# design.net
KiCad netlist of a schematic drawn in Altium Designer
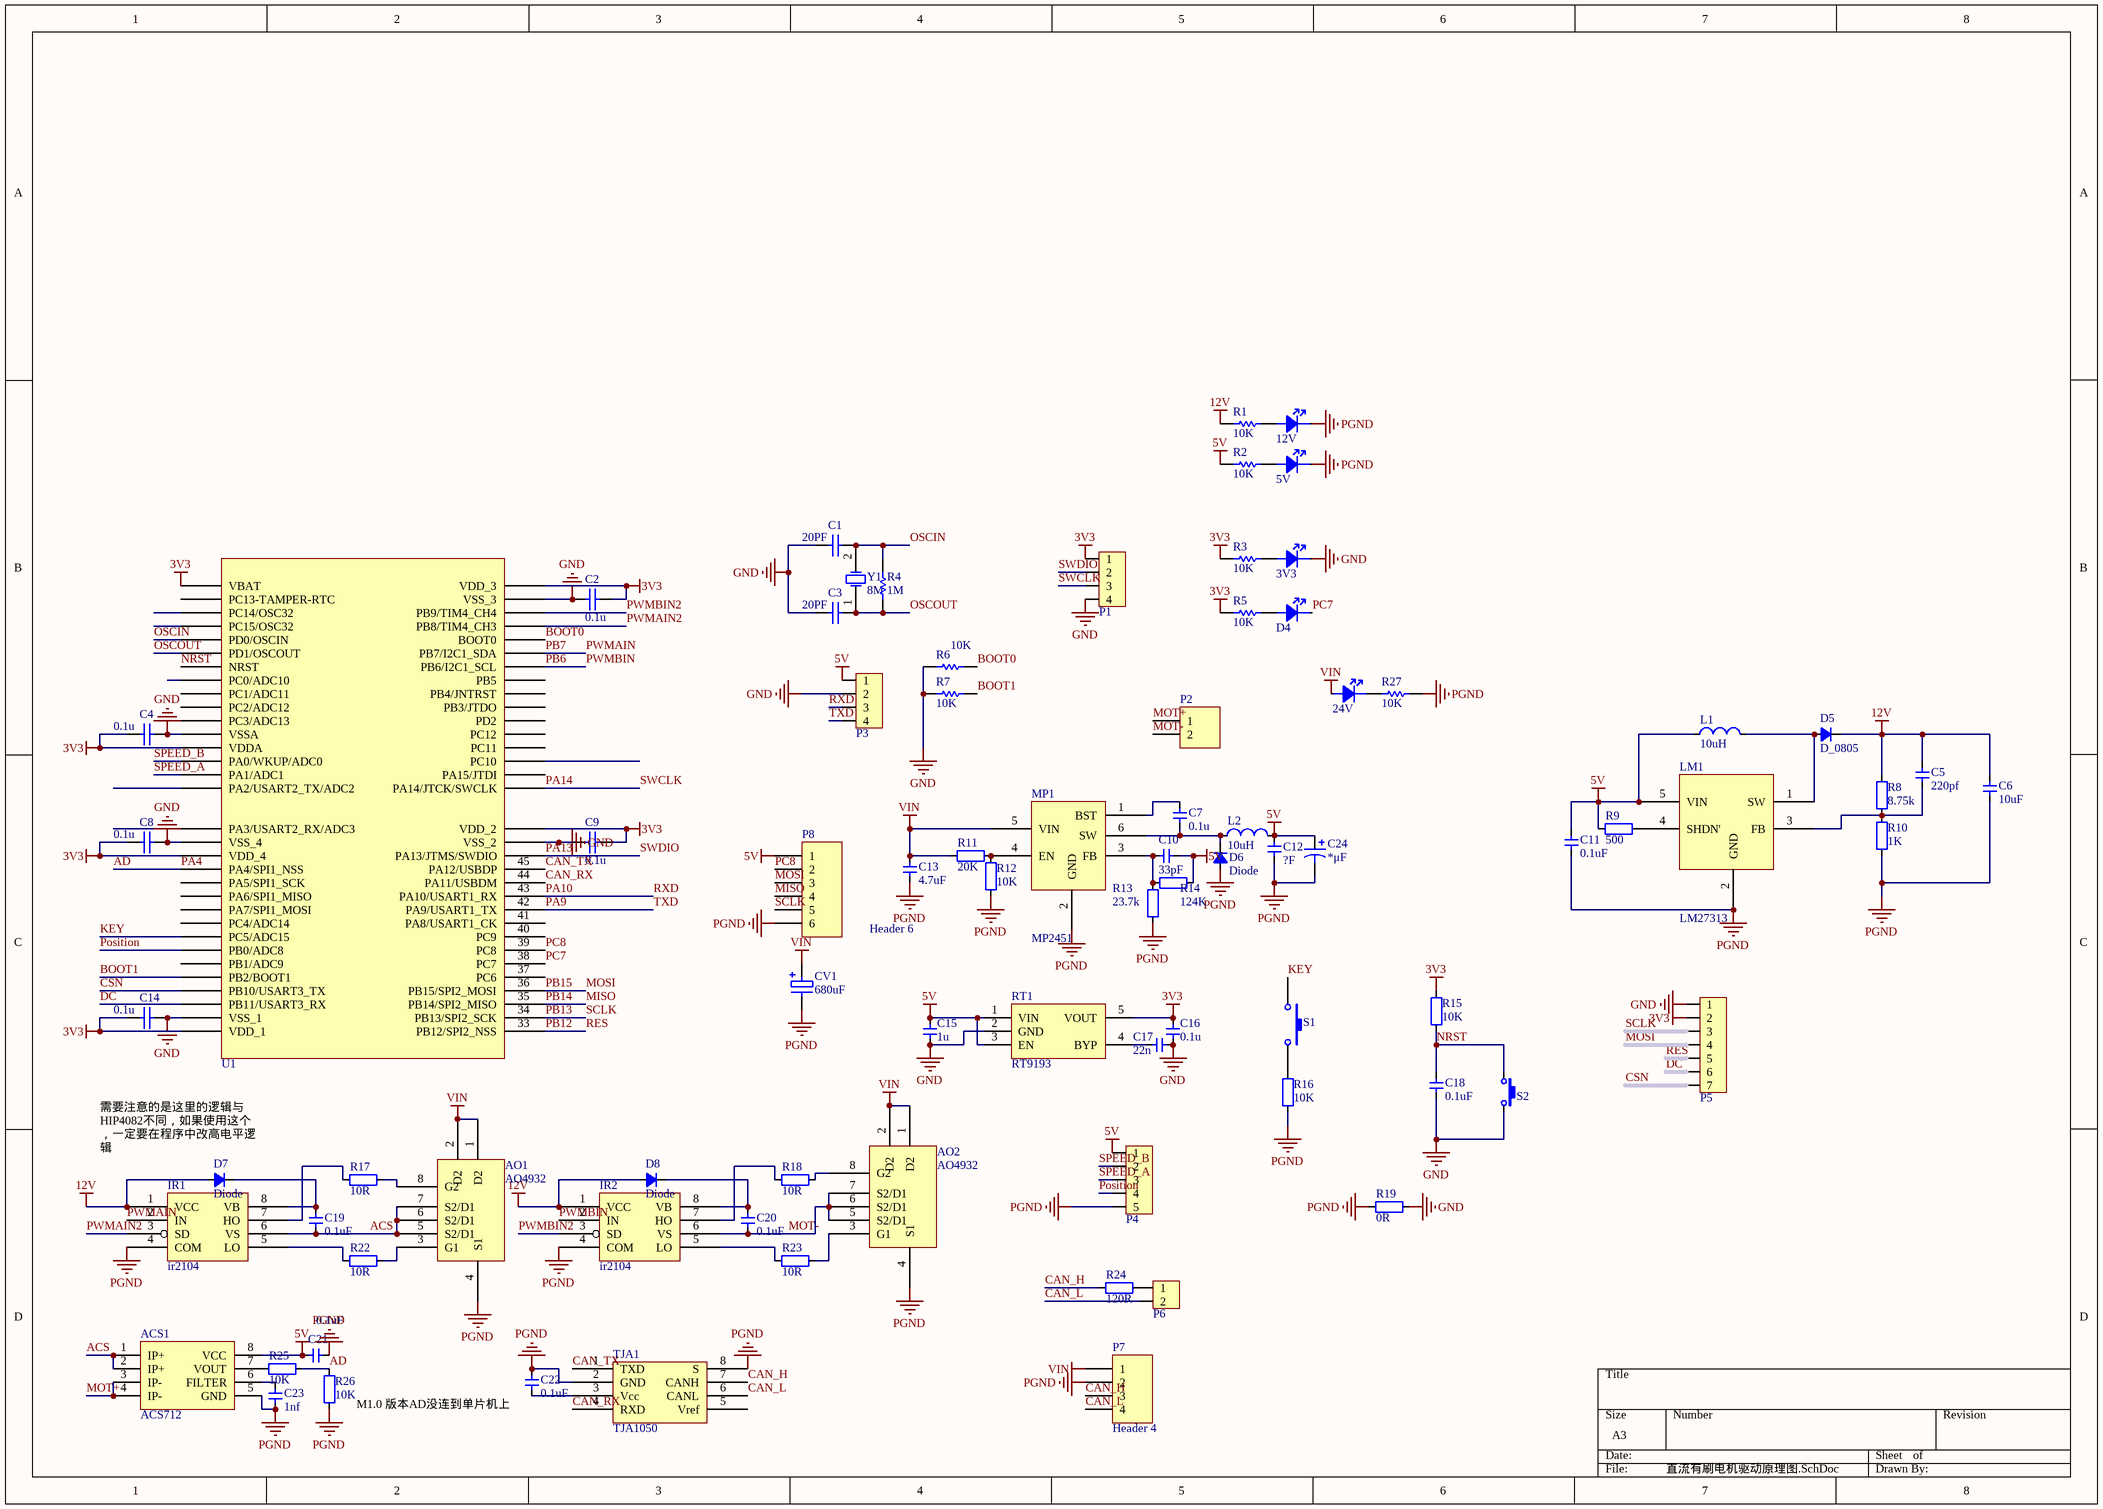
[diagram p0: 直流有刷电机驱动原理图.SchDoc]

(export (version "E")
  (design (tool "Eeschema 10.0.6"))
  (components
    (comp (ref "3V3")
      (value "lED")
      (footprint "0805D")
      (description "LED")
      (libsource (lib "K60-mainboard-v3.1") (part "00-D-LED"))
    )
    (comp (ref "5V")
      (value "lED")
      (footprint "0805D")
      (description "LED")
      (libsource (lib "K60-mainboard-v3.1") (part "00-D-LED"))
    )
    (comp (ref "12V")
      (value "lED")
      (footprint "0805D")
      (description "LED")
      (libsource (lib "K60-mainboard-v3.1") (part "00-D-LED"))
    )
    (comp (ref "24V")
      (value "lED")
      (footprint "0805D")
      (description "LED")
      (libsource (lib "K60-mainboard-v3.1") (part "00-D-LED"))
    )
    (comp (ref "ACS1")
      (value "ACS712")
      (footprint "PCB_IntegratedCircuit:SOP_E150_8")
      (description "Sensor Current")
      (libsource (lib "SCH_IntegratedCircuit") (part "ACS712"))
    )
    (comp (ref "AO1")
      (value "AO4932")
      (footprint "SOP_E150_8")
      (libsource (lib "SCH_Active") (part "AO4932"))
    )
    (comp (ref "AO2")
      (value "AO4932")
      (footprint "SOP_E150_8")
      (libsource (lib "SCH_Active") (part "AO4932"))
    )
    (comp (ref "C1")
      (value "20PF")
      (footprint "CAP-MLCC-0603")
      (description "Capacitor")
      (fields (field (name "Comment") "Cap") (field (name "PUBLISHER") "Altium Limited"))
      (libsource (lib "K60-mainboard-v3.1") (part "Cap_1"))
    )
    (comp (ref "C2")
      (value "0.1u")
      (footprint "CAP-MLCC-0603")
      (description "Capacitor")
      (fields (field (name "Comment") "Cap") (field (name "PUBLISHER") "Altium Limited"))
      (libsource (lib "K60-mainboard-v3.1") (part "Cap_1"))
    )
    (comp (ref "C3")
      (value "20PF")
      (footprint "CAP-MLCC-0603")
      (description "Capacitor")
      (fields (field (name "Comment") "Cap") (field (name "PUBLISHER") "Altium Limited"))
      (libsource (lib "K60-mainboard-v3.1") (part "Cap_1"))
    )
    (comp (ref "C4")
      (value "0.1u")
      (footprint "CAP-MLCC-0603")
      (description "Capacitor")
      (fields (field (name "Comment") "Cap") (field (name "PUBLISHER") "Altium Limited"))
      (libsource (lib "K60-mainboard-v3.1") (part "Cap_1"))
    )
    (comp (ref "C5")
      (value "220pf")
      (footprint "PCB_PassiveCap:CAP_0603")
      (description "Capacitor")
      (fields (field (name "Comment") "Cap_0603"))
      (libsource (lib "SCH_Passive") (part "Cap_0603"))
    )
    (comp (ref "C6")
      (value "10uF")
      (footprint "PCB_PassiveCap:CAP_0603")
      (description "Capacitor")
      (fields (field (name "Comment") "Cap_0603"))
      (libsource (lib "SCH_Passive") (part "Cap_0603"))
    )
    (comp (ref "C7")
      (value "0.1u")
      (footprint "PCB_PassiveCap:CAP_0603")
      (description "Capacitor")
      (fields (field (name "Comment") "Cap_0603"))
      (libsource (lib "SCH_Passive") (part "Cap_0603"))
    )
    (comp (ref "C8")
      (value "0.1u")
      (footprint "CAP-MLCC-0603")
      (description "Capacitor")
      (fields (field (name "Comment") "Cap") (field (name "PUBLISHER") "Altium Limited"))
      (libsource (lib "K60-mainboard-v3.1") (part "Cap_1"))
    )
    (comp (ref "C9")
      (value "0.1u")
      (footprint "CAP-MLCC-0603")
      (description "Capacitor")
      (fields (field (name "Comment") "Cap") (field (name "PUBLISHER") "Altium Limited"))
      (libsource (lib "K60-mainboard-v3.1") (part "Cap_1"))
    )
    (comp (ref "C10")
      (value "33pF")
      (footprint "PCB_PassiveCap:CAP_0603")
      (description "Capacitor")
      (fields (field (name "Comment") "Cap_0603"))
      (libsource (lib "SCH_Passive") (part "Cap_0603"))
    )
    (comp (ref "C11")
      (value "0.1uF")
      (footprint "PCB_PassiveCap:CAP_0603")
      (description "Capacitor")
      (fields (field (name "Comment") "Cap_0603"))
      (libsource (lib "SCH_Passive") (part "Cap_0603"))
    )
    (comp (ref "C12")
      (value "?F")
      (footprint "PCB_PassiveCap:CAP_0603")
      (description "Capacitor")
      (fields (field (name "Comment") "Cap_0603"))
      (libsource (lib "SCH_Passive") (part "Cap_0603"))
    )
    (comp (ref "C13")
      (value "4.7uF")
      (footprint "Libraries_2014_0618:CAP-MLCC-1206")
      (description "Capacitor")
      (fields (field (name "Comment") "Cap_0805"))
      (libsource (lib "SCH_Passive") (part "Cap_0805"))
    )
    (comp (ref "C14")
      (value "0.1u")
      (footprint "CAP-MLCC-0603")
      (description "Capacitor")
      (fields (field (name "Comment") "Cap") (field (name "PUBLISHER") "Altium Limited"))
      (libsource (lib "K60-mainboard-v3.1") (part "Cap_1"))
    )
    (comp (ref "C15")
      (value "1u")
      (footprint "PCB_PassiveCap:CAP_0603")
      (description "Capacitor")
      (fields (field (name "Comment") "Cap_0603"))
      (libsource (lib "SCH_Passive") (part "Cap_0603"))
    )
    (comp (ref "C16")
      (value "0.1u")
      (footprint "PCB_PassiveCap:CAP_0603")
      (description "Capacitor")
      (fields (field (name "Comment") "Cap_0603"))
      (libsource (lib "SCH_Passive") (part "Cap_0603"))
    )
    (comp (ref "C17")
      (value "22n")
      (footprint "PCB_PassiveCap:CAP_0603")
      (description "Capacitor")
      (fields (field (name "Comment") "Cap_0603"))
      (libsource (lib "SCH_Passive") (part "Cap_0603"))
    )
    (comp (ref "C18")
      (value "0.1uF")
      (footprint "PCB_PassiveCap:CAP_0603")
      (description "Capacitor")
      (fields (field (name "Comment") "Cap_0603"))
      (libsource (lib "SCH_Passive") (part "Cap_0603"))
    )
    (comp (ref "C19")
      (value "0.1uF")
      (footprint "PCB_PassiveCap:CAP_0603")
      (description "Capacitor")
      (fields (field (name "Comment") "Cap_0603"))
      (libsource (lib "SCH_Passive") (part "Cap_0603"))
    )
    (comp (ref "C20")
      (value "0.1uF")
      (footprint "PCB_PassiveCap:CAP_0603")
      (description "Capacitor")
      (fields (field (name "Comment") "Cap_0603"))
      (libsource (lib "SCH_Passive") (part "Cap_0603"))
    )
    (comp (ref "C21")
      (value "0.1uF")
      (footprint "PCB_PassiveCap:CAP_0603")
      (description "Capacitor")
      (fields (field (name "Comment") "Cap_0603"))
      (libsource (lib "SCH_Passive") (part "Cap_0603"))
    )
    (comp (ref "C22")
      (value "0.1uF")
      (footprint "PCB_PassiveCap:CAP_0603")
      (description "Capacitor")
      (fields (field (name "Comment") "Cap_0603"))
      (libsource (lib "SCH_Passive") (part "Cap_0603"))
    )
    (comp (ref "C23")
      (value "1nf")
      (footprint "PCB_PassiveCap:CAP_0603")
      (description "Capacitor")
      (fields (field (name "Comment") "Cap_0603"))
      (libsource (lib "SCH_Passive") (part "Cap_0603"))
    )
    (comp (ref "C24")
      (value "*μF")
      (footprint "CAP-TAN-3216/CAPA")
      (description "钽电容")
      (fields (field (name "PUBLISHER") "Altium Limited"))
      (libsource (lib "Libraries_2014_0618") (part "CAP-TAN"))
    )
    (comp (ref "CV1")
      (value "680uF")
      (footprint "C_ELE2")
      (description "电解电容")
      (fields (field (name "PUBLISHER") "Altium Limited"))
      (libsource (lib "Libraries_2014_0618") (part "CAP-ELE"))
    )
    (comp (ref "D4")
      (value "lED")
      (footprint "0805D")
      (description "LED")
      (libsource (lib "K60-mainboard-v3.1") (part "00-D-LED"))
    )
    (comp (ref "D5")
      (value "D_0805")
      (footprint "LED_0805_YELLOW")
      (libsource (lib "SCH_Active") (part "D_0805"))
    )
    (comp (ref "D6") (value "Diode") (footprint "LED_0805_RED") (libsource (lib "SCH_Active") (part "Diode")))
    (comp (ref "D7") (value "Diode") (footprint "LED_0805_RED") (libsource (lib "SCH_Active") (part "Diode")))
    (comp (ref "D8") (value "Diode") (footprint "LED_0805_RED") (libsource (lib "SCH_Active") (part "Diode")))
    (comp (ref "IR1")
      (value "ir2104")
      (footprint "SOP_E150_8")
      (libsource (lib "SCH_IntegratedCircuit") (part "ir2104"))
    )
    (comp (ref "IR2")
      (value "ir2104")
      (footprint "SOP_E150_8")
      (libsource (lib "SCH_IntegratedCircuit") (part "ir2104"))
    )
    (comp (ref "L1")
      (value "10uH")
      (footprint "IND_CD52")
      (description "Inductor")
      (fields (field (name "Comment") "Ind_CD32"))
      (libsource (lib "SCH_Passive") (part "Ind_CD32"))
    )
    (comp (ref "L2")
      (value "10uH")
      (footprint "IND_CD52")
      (description "Inductor")
      (fields (field (name "Comment") "Ind_CD32"))
      (libsource (lib "SCH_Passive") (part "Ind_CD32"))
    )
    (comp (ref "LM1")
      (value "LM27313")
      (footprint "SOT23-5")
      (libsource (lib "SCH_IntegratedCircuit") (part "LM27313"))
    )
    (comp (ref "MP1")
      (value "MP2451")
      (footprint "SOT23-6")
      (libsource (lib "SCH_IntegratedCircuit") (part "MP2451"))
    )
    (comp (ref "P1")
      (value "HDR1x4_2.54")
      (footprint "PCB_ConnectorHDR:HDR1x4_2.54_180")
      (description "Header")
      (libsource (lib "SCH_ConnectorHDR") (part "HDR1x4_2.54"))
    )
    (comp (ref "P2")
      (value "Header 2")
      (footprint "Green_2P")
      (description "Header, 2-Pin")
      (fields (field (name "PUBLISHER") "Altium Limited"))
      (libsource (lib "Libraries_2014_0618") (part "Header 2"))
    )
    (comp (ref "P3")
      (value "HDR1x4_2.54")
      (footprint "PCB_ConnectorHDR:HDR1x4_2.54_180")
      (description "Header")
      (libsource (lib "SCH_ConnectorHDR") (part "HDR1x4_2.54"))
    )
    (comp (ref "P4")
      (value "HDR1x5_2.54")
      (footprint "PCB_ConnectorHDR:HDR1X5_2.54_180")
      (description "Header")
      (libsource (lib "SCH_ConnectorHDR") (part "HDR1x5_2.54"))
    )
    (comp (ref "P5")
      (value "HDR1x7_2.54")
      (footprint "PCB_ConnectorHDR:HDR1X7_2.54_180")
      (description "Header")
      (libsource (lib "SCH_ConnectorHDR") (part "HDR1x7_2.54T"))
    )
    (comp (ref "P6")
      (value "HDR1x2_2.54")
      (footprint "PCB_ConnectorHDR:HDR1X2_2.54_180")
      (description "Header")
      (libsource (lib "SCH_ConnectorHDR") (part "HDR1x2_2.54"))
    )
    (comp (ref "P7")
      (value "Header 4")
      (footprint "Green_4P")
      (description "Header, 4-Pin")
      (fields (field (name "PUBLISHER") "Altium Limited"))
      (libsource (lib "Libraries_2014_0618") (part "Header 4"))
    )
    (comp (ref "P8")
      (value "Header 6")
      (footprint "HDR1X6_2.54_180")
      (description "Header, 6-Pin")
      (fields (field (name "PUBLISHER") "Altium Limited"))
      (libsource (lib "Libraries_2014_0618") (part "Header 6"))
    )
    (comp (ref "R1")
      (value "10K")
      (footprint "RES-0603")
      (description "Resistor")
      (fields (field (name "Comment") "Res1") (field (name "PUBLISHER") "Altium Limited"))
      (libsource (lib "K60-mainboard-v3.1") (part "Res1_1"))
    )
    (comp (ref "R2")
      (value "10K")
      (footprint "RES-0603")
      (description "Resistor")
      (fields (field (name "Comment") "Res1") (field (name "PUBLISHER") "Altium Limited"))
      (libsource (lib "K60-mainboard-v3.1") (part "Res1_1"))
    )
    (comp (ref "R3")
      (value "10K")
      (footprint "RES-0603")
      (description "Resistor")
      (fields (field (name "Comment") "Res1") (field (name "PUBLISHER") "Altium Limited"))
      (libsource (lib "K60-mainboard-v3.1") (part "Res1_1"))
    )
    (comp (ref "R4")
      (value "1M")
      (footprint "RES-0603")
      (description "Resistor")
      (fields (field (name "Comment") "Res1") (field (name "PUBLISHER") "Altium Limited"))
      (libsource (lib "K60-mainboard-v3.1") (part "Res1_1"))
    )
    (comp (ref "R5")
      (value "10K")
      (footprint "RES-0603")
      (description "Resistor")
      (fields (field (name "Comment") "Res1") (field (name "PUBLISHER") "Altium Limited"))
      (libsource (lib "K60-mainboard-v3.1") (part "Res1_1"))
    )
    (comp (ref "R6")
      (value "10K")
      (footprint "RES-0603")
      (description "Resistor")
      (fields (field (name "Comment") "Res1") (field (name "PUBLISHER") "Altium Limited"))
      (libsource (lib "K60-mainboard-v3.1") (part "Res1_1"))
    )
    (comp (ref "R7")
      (value "10K")
      (footprint "RES-0603")
      (description "Resistor")
      (fields (field (name "Comment") "Res1") (field (name "PUBLISHER") "Altium Limited"))
      (libsource (lib "K60-mainboard-v3.1") (part "Res1_1"))
    )
    (comp (ref "R8")
      (value "8.75k")
      (footprint "PCB_PassiveRes:RES_0603")
      (description "Resistor")
      (fields (field (name "Comment") "Res_0603"))
      (libsource (lib "SCH_Passive") (part "Res_0603"))
    )
    (comp (ref "R9")
      (value "500")
      (footprint "PCB_PassiveRes:RES_0603")
      (description "Resistor")
      (fields (field (name "Comment") "Res_0603"))
      (libsource (lib "") (part "Res_0603_2"))
    )
    (comp (ref "R10")
      (value "1K")
      (footprint "PCB_PassiveRes:RES_0603")
      (description "Resistor")
      (fields (field (name "Comment") "Res_0603"))
      (libsource (lib "SCH_Passive") (part "Res_0603"))
    )
    (comp (ref "R11")
      (value "20K")
      (footprint "PCB_PassiveRes:RES_0603")
      (description "Resistor")
      (fields (field (name "Comment") "Res_0603"))
      (libsource (lib "") (part "Res_0603_3"))
    )
    (comp (ref "R12")
      (value "10K")
      (footprint "PCB_PassiveRes:RES_0603")
      (description "Resistor")
      (fields (field (name "Comment") "Res_0603"))
      (libsource (lib "SCH_Passive") (part "Res_0603"))
    )
    (comp (ref "R13")
      (value "23.7k")
      (footprint "PCB_PassiveRes:RES_0603")
      (description "Resistor")
      (fields (field (name "Comment") "Res_0603"))
      (libsource (lib "SCH_Passive") (part "Res_0603"))
    )
    (comp (ref "R14")
      (value "124K")
      (footprint "PCB_PassiveRes:RES_0603")
      (description "Resistor")
      (fields (field (name "Comment") "Res_0603"))
      (libsource (lib "") (part "Res_0603_3"))
    )
    (comp (ref "R15")
      (value "10K")
      (footprint "PCB_PassiveRes:RES_0603")
      (description "Resistor")
      (fields (field (name "Comment") "Res_0603"))
      (libsource (lib "") (part "Res_0603_1"))
    )
    (comp (ref "R16")
      (value "10K")
      (footprint "PCB_PassiveRes:RES_0603")
      (description "Resistor")
      (fields (field (name "Comment") "Res_0603"))
      (libsource (lib "SCH_Passive") (part "Res_0603"))
    )
    (comp (ref "R17")
      (value "10R")
      (footprint "PCB_PassiveRes:RES_0603")
      (description "Resistor")
      (fields (field (name "Comment") "Res_0603"))
      (libsource (lib "") (part "Res_0603_3"))
    )
    (comp (ref "R18")
      (value "10R")
      (footprint "PCB_PassiveRes:RES_0603")
      (description "Resistor")
      (fields (field (name "Comment") "Res_0603"))
      (libsource (lib "") (part "Res_0603_3"))
    )
    (comp (ref "R19")
      (value "0R")
      (footprint "PCB_PassiveRes:RES_0603")
      (description "Resistor")
      (fields (field (name "Comment") "Res_0603"))
      (libsource (lib "") (part "Res_0603_2"))
    )
    (comp (ref "R22")
      (value "10R")
      (footprint "PCB_PassiveRes:RES_0603")
      (description "Resistor")
      (fields (field (name "Comment") "Res_0603"))
      (libsource (lib "") (part "Res_0603_3"))
    )
    (comp (ref "R23")
      (value "10R")
      (footprint "PCB_PassiveRes:RES_0603")
      (description "Resistor")
      (fields (field (name "Comment") "Res_0603"))
      (libsource (lib "") (part "Res_0603_3"))
    )
    (comp (ref "R24")
      (value "120R")
      (footprint "PCB_PassiveRes:RES_0603")
      (description "Resistor")
      (fields (field (name "Comment") "Res_0603"))
      (libsource (lib "") (part "Res_0603_2"))
    )
    (comp (ref "R25")
      (value "10K")
      (footprint "PCB_PassiveRes:RES_0603")
      (description "Resistor")
      (fields (field (name "Comment") "Res_0603"))
      (libsource (lib "") (part "Res_0603_3"))
    )
    (comp (ref "R26")
      (value "10K")
      (footprint "PCB_PassiveRes:RES_0603")
      (description "Resistor")
      (fields (field (name "Comment") "Res_0603"))
      (libsource (lib "") (part "Res_0603_1"))
    )
    (comp (ref "R27")
      (value "10K")
      (footprint "RES-0603")
      (description "Resistor")
      (fields (field (name "Comment") "Res1") (field (name "PUBLISHER") "Altium Limited"))
      (libsource (lib "K60-mainboard-v3.1") (part "Res1_1"))
    )
    (comp (ref "RT1")
      (value "RT9193")
      (footprint "PCB_IntegratedCircuit:SOT23-5")
      (description "Power")
      (libsource (lib "SCH_IntegratedCircuit") (part "RT9193"))
    )
    (comp (ref "S1")
      (value "SW-PB")
      (footprint "key - duplicate")
      (description "Switch")
      (fields (field (name "PUBLISHER") "Altium Limited"))
      (libsource (lib "附加元件") (part "SW-PB"))
    )
    (comp (ref "S2")
      (value "ButtonTACT_3x4x2_180")
      (footprint "PCB_Switch:ButtonTACT_3x4x2_180H")
      (description "Button")
      (libsource (lib "SCH_Switch") (part "ButtonTACT_3x4x2_180"))
    )
    (comp (ref "TJA1")
      (value "TJA1050")
      (footprint "SOP_E150_8")
      (libsource (lib "SCH_IntegratedCircuit") (part "TJA1050"))
    )
    (comp (ref "U1")
      (value "STM32F103RC")
      (footprint "LQFP_P0.5_64")
      (description "MCU")
      (libsource (lib "SCH_IntegratedCircuit") (part "STM32F103RC"))
    )
    (comp (ref "Y1")
      (value "8M")
      (footprint "PCB_Oscillator:XT_5032_2")
      (description "Crystal Oscillator")
      (fields (field (name "PUBLISHER") "Altium Limited"))
      (libsource (lib "Libraries_2014_0618") (part "C-Osc"))
    )
  )
  (nets
    (net (code "1") (name "/ACS") (class "Default")
      (node (ref "ACS1") (pin "1") (pinfunction "IP+_1") (pintype "passive"))
      (node (ref "ACS1") (pin "2") (pinfunction "IP+_2") (pintype "passive"))
      (node (ref "AO1") (pin "5") (pinfunction "S2/D1_5") (pintype "passive"))
      (node (ref "AO1") (pin "6") (pinfunction "S2/D1_6") (pintype "passive"))
      (node (ref "AO1") (pin "7") (pinfunction "S2/D1_7") (pintype "passive"))
      (node (ref "C19") (pin "2") (pinfunction "2_2") (pintype "passive"))
      (node (ref "IR1") (pin "6") (pinfunction "VS_6") (pintype "passive"))
    )
    (net (code "2") (name "/AD") (class "Default")
      (node (ref "R25") (pin "2") (pinfunction "2_2") (pintype "passive"))
      (node (ref "R26") (pin "2") (pinfunction "2_2") (pintype "passive"))
      (node (ref "U1") (pin "20") (pinfunction "PA4/SPI1_NSS_20") (pintype "passive"))
    )
    (net (code "3") (name "/BOOT0") (class "Default")
      (node (ref "R6") (pin "1") (pinfunction "1_1") (pintype "passive"))
      (node (ref "U1") (pin "60") (pinfunction "BOOT0_60") (pintype "passive"))
    )
    (net (code "4") (name "/BOOT1") (class "Default")
      (node (ref "R7") (pin "1") (pinfunction "1_1") (pintype "passive"))
      (node (ref "U1") (pin "28") (pinfunction "PB2/BOOT1_28") (pintype "passive"))
    )
    (net (code "5") (name "/CAN_H") (class "Default")
      (node (ref "P7") (pin "3") (pinfunction "3_3") (pintype "passive"))
      (node (ref "R24") (pin "2") (pinfunction "2_2") (pintype "passive"))
      (node (ref "TJA1") (pin "7") (pinfunction "CANH_7") (pintype "passive"))
    )
    (net (code "6") (name "/CAN_L") (class "Default")
      (node (ref "P6") (pin "2") (pinfunction "2_2") (pintype "passive"))
      (node (ref "P7") (pin "4") (pinfunction "4_4") (pintype "passive"))
      (node (ref "TJA1") (pin "6") (pinfunction "CANL_6") (pintype "passive"))
    )
    (net (code "7") (name "/CAN_RX") (class "Default")
      (node (ref "TJA1") (pin "4") (pinfunction "RXD_4") (pintype "passive"))
      (node (ref "U1") (pin "44") (pinfunction "PA11/USBDM_44") (pintype "passive"))
    )
    (net (code "8") (name "/CAN_TX") (class "Default")
      (node (ref "TJA1") (pin "1") (pinfunction "TXD_1") (pintype "passive"))
      (node (ref "U1") (pin "45") (pinfunction "PA12/USBDP_45") (pintype "passive"))
    )
    (net (code "9") (name "/CSN") (class "Default")
      (node (ref "P5") (pin "7") (pinfunction "7_7") (pintype "passive"))
      (node (ref "U1") (pin "29") (pinfunction "PB10/USART3_TX_29") (pintype "passive"))
    )
    (net (code "10") (name "/DC") (class "Default")
      (node (ref "P5") (pin "6") (pinfunction "6_6") (pintype "passive"))
      (node (ref "U1") (pin "30") (pinfunction "PB11/USART3_RX_30") (pintype "passive"))
    )
    (net (code "11") (name "/KEY") (class "Default")
      (node (ref "S1") (pin "1") (pinfunction "1_1") (pintype "passive"))
      (node (ref "U1") (pin "25") (pinfunction "PC5/ADC15_25") (pintype "passive"))
    )
    (net (code "12") (name "/MISO") (class "Default")
      (node (ref "P8") (pin "4") (pinfunction "4_4") (pintype "passive"))
      (node (ref "U1") (pin "35") (pinfunction "PB14/SPI2_MISO_35") (pintype "passive"))
    )
    (net (code "13") (name "/MOSI") (class "Default")
      (node (ref "P5") (pin "4") (pinfunction "4_4") (pintype "passive"))
      (node (ref "P8") (pin "3") (pinfunction "3_3") (pintype "passive"))
      (node (ref "U1") (pin "36") (pinfunction "PB15/SPI2_MOSI_36") (pintype "passive"))
    )
    (net (code "14") (name "/MOT+") (class "Default")
      (node (ref "ACS1") (pin "3") (pinfunction "IP-_3") (pintype "passive"))
      (node (ref "ACS1") (pin "4") (pinfunction "IP-_4") (pintype "passive"))
      (node (ref "P2") (pin "1") (pinfunction "1_1") (pintype "passive"))
    )
    (net (code "15") (name "/MOT-") (class "Default")
      (node (ref "AO2") (pin "5") (pinfunction "S2/D1_5") (pintype "passive"))
      (node (ref "AO2") (pin "6") (pinfunction "S2/D1_6") (pintype "passive"))
      (node (ref "AO2") (pin "7") (pinfunction "S2/D1_7") (pintype "passive"))
      (node (ref "C20") (pin "2") (pinfunction "2_2") (pintype "passive"))
      (node (ref "IR2") (pin "6") (pinfunction "VS_6") (pintype "passive"))
      (node (ref "P2") (pin "2") (pinfunction "2_2") (pintype "passive"))
    )
    (net (code "16") (name "/NRST") (class "Default")
      (node (ref "C18") (pin "1") (pinfunction "1_1") (pintype "passive"))
      (node (ref "R15") (pin "1") (pinfunction "1_1") (pintype "passive"))
      (node (ref "S2") (pin "1") (pinfunction "1_1") (pintype "passive"))
      (node (ref "U1") (pin "7") (pinfunction "NRST_7") (pintype "passive"))
    )
    (net (code "17") (name "/OSCIN") (class "Default")
      (node (ref "C1") (pin "2") (pinfunction "2_2") (pintype "passive"))
      (node (ref "R4") (pin "2") (pinfunction "2_2") (pintype "passive"))
      (node (ref "U1") (pin "5") (pinfunction "PD0/OSCIN_5") (pintype "passive"))
      (node (ref "Y1") (pin "2") (pinfunction "OSC2_2") (pintype "passive"))
    )
    (net (code "18") (name "/OSCOUT") (class "Default")
      (node (ref "C3") (pin "2") (pinfunction "2_2") (pintype "passive"))
      (node (ref "R4") (pin "1") (pinfunction "1_1") (pintype "passive"))
      (node (ref "U1") (pin "6") (pinfunction "PD1/OSCOUT_6") (pintype "passive"))
      (node (ref "Y1") (pin "1") (pinfunction "OSC1_1") (pintype "passive"))
    )
    (net (code "19") (name "/PA9") (class "Default")
      (node (ref "P3") (pin "4") (pinfunction "4_4") (pintype "passive"))
      (node (ref "U1") (pin "42") (pinfunction "PA9/USART1_TX_42") (pintype "passive"))
    )
    (net (code "20") (name "/PA10") (class "Default")
      (node (ref "P3") (pin "3") (pinfunction "3_3") (pintype "passive"))
      (node (ref "U1") (pin "43") (pinfunction "PA10/USART1_RX_43") (pintype "passive"))
    )
    (net (code "21") (name "/PA13") (class "Default")
      (node (ref "P1") (pin "2") (pinfunction "2_2") (pintype "passive"))
      (node (ref "U1") (pin "46") (pinfunction "PA13/JTMS/SWDIO_46") (pintype "passive"))
    )
    (net (code "22") (name "/PA14") (class "Default")
      (node (ref "P1") (pin "3") (pinfunction "3_3") (pintype "passive"))
      (node (ref "U1") (pin "49") (pinfunction "PA14/JTCK/SWCLK_49") (pintype "passive"))
    )
    (net (code "23") (name "/PB6") (class "Default")
      (node (ref "IR2") (pin "2") (pinfunction "IN_2") (pintype "passive"))
      (node (ref "U1") (pin "58") (pinfunction "PB6/I2C1_SCL_58") (pintype "passive"))
    )
    (net (code "24") (name "/PB7") (class "Default")
      (node (ref "IR1") (pin "2") (pinfunction "IN_2") (pintype "passive"))
      (node (ref "U1") (pin "59") (pinfunction "PB7/I2C1_SDA_59") (pintype "passive"))
    )
    (net (code "25") (name "/PB12") (class "Default")
      (node (ref "P5") (pin "5") (pinfunction "5_5") (pintype "passive"))
      (node (ref "U1") (pin "33") (pinfunction "PB12/SPI2_NSS_33") (pintype "passive"))
    )
    (net (code "26") (name "/PB13") (class "Default")
      (node (ref "P5") (pin "3") (pinfunction "3_3") (pintype "passive"))
      (node (ref "P8") (pin "5") (pinfunction "5_5") (pintype "passive"))
      (node (ref "U1") (pin "34") (pinfunction "PB13/SPI2_SCK_34") (pintype "passive"))
    )
    (net (code "27") (name "/PC7") (class "Default")
      (node (ref "D4") (pin "K") (pinfunction "2_K") (pintype "passive"))
      (node (ref "U1") (pin "38") (pinfunction "PC7_38") (pintype "passive"))
    )
    (net (code "28") (name "/PC8") (class "Default")
      (node (ref "P8") (pin "2") (pinfunction "2_2") (pintype "passive"))
      (node (ref "U1") (pin "39") (pinfunction "PC8_39") (pintype "passive"))
    )
    (net (code "29") (name "/PWMAIN2") (class "Default")
      (node (ref "IR1") (pin "3") (pinfunction "SD_3") (pintype "passive"))
      (node (ref "U1") (pin "61") (pinfunction "PB8/TIM4_CH3_61") (pintype "passive"))
    )
    (net (code "30") (name "/PWMBIN2") (class "Default")
      (node (ref "IR2") (pin "3") (pinfunction "SD_3") (pintype "passive"))
      (node (ref "U1") (pin "62") (pinfunction "PB9/TIM4_CH4_62") (pintype "passive"))
    )
    (net (code "31") (name "/Position") (class "Default")
      (node (ref "P4") (pin "4") (pinfunction "4_4") (pintype "passive"))
      (node (ref "U1") (pin "26") (pinfunction "PB0/ADC8_26") (pintype "passive"))
    )
    (net (code "32") (name "/SPEED_A") (class "Default")
      (node (ref "P4") (pin "3") (pinfunction "3_3") (pintype "passive"))
      (node (ref "U1") (pin "15") (pinfunction "PA1/ADC1_15") (pintype "passive"))
    )
    (net (code "33") (name "/SPEED_B") (class "Default")
      (node (ref "P4") (pin "2") (pinfunction "2_2") (pintype "passive"))
      (node (ref "U1") (pin "14") (pinfunction "PA0/WKUP/ADC0_14") (pintype "passive"))
    )
    (net (code "34") (name "3V3") (class "Default")
      (node (ref "C14") (pin "1") (pinfunction "1_1") (pintype "passive"))
      (node (ref "C16") (pin "2") (pinfunction "2_2") (pintype "passive"))
      (node (ref "C2") (pin "1") (pinfunction "1_1") (pintype "passive"))
      (node (ref "C4") (pin "1") (pinfunction "1_1") (pintype "passive"))
      (node (ref "C8") (pin "1") (pinfunction "1_1") (pintype "passive"))
      (node (ref "C9") (pin "1") (pinfunction "1_1") (pintype "passive"))
      (node (ref "P1") (pin "1") (pinfunction "1_1") (pintype "passive"))
      (node (ref "P5") (pin "2") (pinfunction "2_2") (pintype "passive"))
      (node (ref "R15") (pin "2") (pinfunction "2_2") (pintype "passive"))
      (node (ref "R3") (pin "2") (pinfunction "2_2") (pintype "passive"))
      (node (ref "R5") (pin "2") (pinfunction "2_2") (pintype "passive"))
      (node (ref "RT1") (pin "5") (pinfunction "VOUT_5") (pintype "passive"))
      (node (ref "U1") (pin "1") (pinfunction "VBAT_1") (pintype "passive"))
      (node (ref "U1") (pin "13") (pinfunction "VDDA_13") (pintype "passive"))
      (node (ref "U1") (pin "19") (pinfunction "VDD_4_19") (pintype "passive"))
      (node (ref "U1") (pin "32") (pinfunction "VDD_1_32") (pintype "passive"))
      (node (ref "U1") (pin "48") (pinfunction "VDD_2_48") (pintype "passive"))
      (node (ref "U1") (pin "64") (pinfunction "VDD_3_64") (pintype "passive"))
    )
    (net (code "35") (name "5V") (class "Default")
      (node (ref "ACS1") (pin "8") (pinfunction "VCC_8") (pintype "passive"))
      (node (ref "C10") (pin "1") (pinfunction "1_1") (pintype "passive"))
      (node (ref "C11") (pin "1") (pinfunction "1_1") (pintype "passive"))
      (node (ref "C12") (pin "2") (pinfunction "2_2") (pintype "passive"))
      (node (ref "C15") (pin "2") (pinfunction "2_2") (pintype "passive"))
      (node (ref "C21") (pin "1") (pinfunction "1_1") (pintype "passive"))
      (node (ref "C24") (pin "1") (pinfunction "1_1") (pintype "passive"))
      (node (ref "L1") (pin "1") (pinfunction "1_1") (pintype "passive"))
      (node (ref "L2") (pin "2") (pinfunction "2_2") (pintype "passive"))
      (node (ref "LM1") (pin "5") (pinfunction "VIN_5") (pintype "passive"))
      (node (ref "P3") (pin "1") (pinfunction "1_1") (pintype "passive"))
      (node (ref "P4") (pin "1") (pinfunction "1_1") (pintype "passive"))
      (node (ref "P8") (pin "1") (pinfunction "1_1") (pintype "passive"))
      (node (ref "R14") (pin "2") (pinfunction "2_2") (pintype "passive"))
      (node (ref "R2") (pin "2") (pinfunction "2_2") (pintype "passive"))
      (node (ref "R9") (pin "2") (pinfunction "2_2") (pintype "passive"))
      (node (ref "RT1") (pin "1") (pinfunction "VIN_1") (pintype "passive"))
      (node (ref "RT1") (pin "3") (pinfunction "EN_3") (pintype "power_in"))
    )
    (net (code "36") (name "12V") (class "Default")
      (node (ref "C5") (pin "1") (pinfunction "1_1") (pintype "passive"))
      (node (ref "C6") (pin "2") (pinfunction "2_2") (pintype "passive"))
      (node (ref "D5") (pin "2") (pinfunction "K_2") (pintype "passive"))
      (node (ref "D7") (pin "1") (pinfunction "A_1") (pintype "passive"))
      (node (ref "D8") (pin "1") (pinfunction "A_1") (pintype "passive"))
      (node (ref "IR1") (pin "1") (pinfunction "VCC_1") (pintype "passive"))
      (node (ref "IR2") (pin "1") (pinfunction "VCC_1") (pintype "passive"))
      (node (ref "R1") (pin "2") (pinfunction "2_2") (pintype "passive"))
      (node (ref "R8") (pin "1") (pinfunction "1_1") (pintype "passive"))
    )
    (net (code "37") (name "GND") (class "Default")
      (node (ref "3V3") (pin "K") (pinfunction "2_K") (pintype "passive"))
      (node (ref "C1") (pin "1") (pinfunction "1_1") (pintype "passive"))
      (node (ref "C14") (pin "2") (pinfunction "2_2") (pintype "passive"))
      (node (ref "C15") (pin "1") (pinfunction "1_1") (pintype "passive"))
      (node (ref "C16") (pin "1") (pinfunction "1_1") (pintype "passive"))
      (node (ref "C17") (pin "1") (pinfunction "1_1") (pintype "passive"))
      (node (ref "C18") (pin "2") (pinfunction "2_2") (pintype "passive"))
      (node (ref "C2") (pin "2") (pinfunction "2_2") (pintype "passive"))
      (node (ref "C3") (pin "1") (pinfunction "1_1") (pintype "passive"))
      (node (ref "C4") (pin "2") (pinfunction "2_2") (pintype "passive"))
      (node (ref "C8") (pin "2") (pinfunction "2_2") (pintype "passive"))
      (node (ref "C9") (pin "2") (pinfunction "2_2") (pintype "passive"))
      (node (ref "P1") (pin "4") (pinfunction "4_4") (pintype "passive"))
      (node (ref "P3") (pin "2") (pinfunction "2_2") (pintype "passive"))
      (node (ref "P5") (pin "1") (pinfunction "1_1") (pintype "passive"))
      (node (ref "R19") (pin "1") (pinfunction "1_1") (pintype "passive"))
      (node (ref "R6") (pin "2") (pinfunction "2_2") (pintype "passive"))
      (node (ref "R7") (pin "2") (pinfunction "2_2") (pintype "passive"))
      (node (ref "RT1") (pin "2") (pinfunction "GND_2") (pintype "passive"))
      (node (ref "S2") (pin "2") (pinfunction "2_2") (pintype "passive"))
      (node (ref "U1") (pin "12") (pinfunction "VSSA_12") (pintype "passive"))
      (node (ref "U1") (pin "18") (pinfunction "VSS_4_18") (pintype "passive"))
      (node (ref "U1") (pin "31") (pinfunction "VSS_1_31") (pintype "passive"))
      (node (ref "U1") (pin "47") (pinfunction "VSS_2_47") (pintype "passive"))
      (node (ref "U1") (pin "63") (pinfunction "VSS_3_63") (pintype "passive"))
    )
    (net (code "38") (name "Net-(3V3-1)") (class "Default")
      (node (ref "3V3") (pin "A") (pinfunction "1_A") (pintype "passive"))
      (node (ref "R3") (pin "1") (pinfunction "1_1") (pintype "passive"))
    )
    (net (code "39") (name "Net-(5V-1)") (class "Default")
      (node (ref "5V") (pin "A") (pinfunction "1_A") (pintype "passive"))
      (node (ref "R2") (pin "1") (pinfunction "1_1") (pintype "passive"))
    )
    (net (code "40") (name "Net-(12V-1)") (class "Default")
      (node (ref "12V") (pin "A") (pinfunction "1_A") (pintype "passive"))
      (node (ref "R1") (pin "1") (pinfunction "1_1") (pintype "passive"))
    )
    (net (code "41") (name "Net-(24V-2)") (class "Default")
      (node (ref "24V") (pin "K") (pinfunction "2_K") (pintype "passive"))
      (node (ref "R27") (pin "2") (pinfunction "2_2") (pintype "passive"))
    )
    (net (code "42") (name "Net-(ACS1-FILTER)") (class "Default")
      (node (ref "ACS1") (pin "6") (pinfunction "FILTER_6") (pintype "passive"))
      (node (ref "C23") (pin "1") (pinfunction "1_1") (pintype "passive"))
    )
    (net (code "43") (name "Net-(ACS1-VOUT)") (class "Default")
      (node (ref "ACS1") (pin "7") (pinfunction "VOUT_7") (pintype "passive"))
      (node (ref "R25") (pin "1") (pinfunction "1_1") (pintype "passive"))
    )
    (net (code "44") (name "Net-(AO1-G1)") (class "Default")
      (node (ref "AO1") (pin "3") (pinfunction "G1_3") (pintype "passive"))
      (node (ref "R22") (pin "2") (pinfunction "2_2") (pintype "passive"))
    )
    (net (code "45") (name "Net-(AO1-G2)") (class "Default")
      (node (ref "AO1") (pin "8") (pinfunction "G2_8") (pintype "passive"))
      (node (ref "R17") (pin "2") (pinfunction "2_2") (pintype "passive"))
    )
    (net (code "46") (name "Net-(AO2-G1)") (class "Default")
      (node (ref "AO2") (pin "3") (pinfunction "G1_3") (pintype "passive"))
      (node (ref "R23") (pin "2") (pinfunction "2_2") (pintype "passive"))
    )
    (net (code "47") (name "Net-(AO2-G2)") (class "Default")
      (node (ref "AO2") (pin "8") (pinfunction "G2_8") (pintype "passive"))
      (node (ref "R18") (pin "2") (pinfunction "2_2") (pintype "passive"))
    )
    (net (code "48") (name "Net-(D4-1)") (class "Default")
      (node (ref "D4") (pin "A") (pinfunction "1_A") (pintype "passive"))
      (node (ref "R5") (pin "1") (pinfunction "1_1") (pintype "passive"))
    )
    (net (code "49") (name "Net-(D5-A)") (class "Default")
      (node (ref "D5") (pin "1") (pinfunction "A_1") (pintype "passive"))
      (node (ref "L1") (pin "2") (pinfunction "2_2") (pintype "passive"))
      (node (ref "LM1") (pin "1") (pinfunction "SW_1") (pintype "passive"))
    )
    (net (code "50") (name "Net-(D6-K)") (class "Default")
      (node (ref "C7") (pin "1") (pinfunction "1_1") (pintype "passive"))
      (node (ref "D6") (pin "2") (pinfunction "K_2") (pintype "passive"))
      (node (ref "L2") (pin "1") (pinfunction "1_1") (pintype "passive"))
      (node (ref "MP1") (pin "6") (pinfunction "SW_6") (pintype "passive"))
    )
    (net (code "51") (name "Net-(D7-K)") (class "Default")
      (node (ref "C19") (pin "1") (pinfunction "1_1") (pintype "passive"))
      (node (ref "D7") (pin "2") (pinfunction "K_2") (pintype "passive"))
      (node (ref "IR1") (pin "8") (pinfunction "VB_8") (pintype "passive"))
    )
    (net (code "52") (name "Net-(D8-K)") (class "Default")
      (node (ref "C20") (pin "1") (pinfunction "1_1") (pintype "passive"))
      (node (ref "D8") (pin "2") (pinfunction "K_2") (pintype "passive"))
      (node (ref "IR2") (pin "8") (pinfunction "VB_8") (pintype "passive"))
    )
    (net (code "53") (name "Net-(IR1-HO)") (class "Default")
      (node (ref "IR1") (pin "7") (pinfunction "HO_7") (pintype "passive"))
      (node (ref "R17") (pin "1") (pinfunction "1_1") (pintype "passive"))
    )
    (net (code "54") (name "Net-(IR1-LO)") (class "Default")
      (node (ref "IR1") (pin "5") (pinfunction "LO_5") (pintype "passive"))
      (node (ref "R22") (pin "1") (pinfunction "1_1") (pintype "passive"))
    )
    (net (code "55") (name "Net-(IR2-HO)") (class "Default")
      (node (ref "IR2") (pin "7") (pinfunction "HO_7") (pintype "passive"))
      (node (ref "R18") (pin "1") (pinfunction "1_1") (pintype "passive"))
    )
    (net (code "56") (name "Net-(IR2-LO)") (class "Default")
      (node (ref "IR2") (pin "5") (pinfunction "LO_5") (pintype "passive"))
      (node (ref "R23") (pin "1") (pinfunction "1_1") (pintype "passive"))
    )
    (net (code "57") (name "Net-(LM1-FB)") (class "Default")
      (node (ref "C5") (pin "2") (pinfunction "2_2") (pintype "passive"))
      (node (ref "LM1") (pin "3") (pinfunction "FB_3") (pintype "passive"))
      (node (ref "R10") (pin "1") (pinfunction "1_1") (pintype "passive"))
      (node (ref "R8") (pin "2") (pinfunction "2_2") (pintype "passive"))
    )
    (net (code "58") (name "Net-(LM1-SHDN')") (class "Default")
      (node (ref "LM1") (pin "4") (pinfunction "SHDN'_4") (pintype "passive"))
      (node (ref "R9") (pin "1") (pinfunction "1_1") (pintype "passive"))
    )
    (net (code "59") (name "Net-(MP1-BST)") (class "Default")
      (node (ref "C7") (pin "2") (pinfunction "2_2") (pintype "passive"))
      (node (ref "MP1") (pin "1") (pinfunction "BST_1") (pintype "passive"))
    )
    (net (code "60") (name "Net-(MP1-EN)") (class "Default")
      (node (ref "MP1") (pin "4") (pinfunction "EN_4") (pintype "passive"))
      (node (ref "R11") (pin "2") (pinfunction "2_2") (pintype "passive"))
      (node (ref "R12") (pin "1") (pinfunction "1_1") (pintype "passive"))
    )
    (net (code "61") (name "Net-(MP1-FB)") (class "Default")
      (node (ref "C10") (pin "2") (pinfunction "2_2") (pintype "passive"))
      (node (ref "MP1") (pin "3") (pinfunction "FB_3") (pintype "passive"))
      (node (ref "R13") (pin "1") (pinfunction "1_1") (pintype "passive"))
      (node (ref "R14") (pin "1") (pinfunction "1_1") (pintype "passive"))
    )
    (net (code "62") (name "Net-(P6-Pad1)") (class "Default")
      (node (ref "P6") (pin "1") (pinfunction "1_1") (pintype "passive"))
      (node (ref "R24") (pin "1") (pinfunction "1_1") (pintype "passive"))
    )
    (net (code "63") (name "Net-(R16-Pad1)") (class "Default")
      (node (ref "R16") (pin "1") (pinfunction "1_1") (pintype "passive"))
      (node (ref "S1") (pin "2") (pinfunction "2_2") (pintype "passive"))
    )
    (net (code "64") (name "Net-(RT1-BYP)") (class "Default")
      (node (ref "C17") (pin "2") (pinfunction "2_2") (pintype "passive"))
      (node (ref "RT1") (pin "4") (pinfunction "BYP_4") (pintype "passive"))
    )
    (net (code "65") (name "Net-(TJA1-Vcc)") (class "Default")
      (node (ref "C22") (pin "1") (pinfunction "1_1") (pintype "passive"))
      (node (ref "TJA1") (pin "3") (pinfunction "Vcc_3") (pintype "passive"))
    )
    (net (code "66") (name "PGND") (class "Default")
      (node (ref "12V") (pin "K") (pinfunction "2_K") (pintype "passive"))
      (node (ref "5V") (pin "K") (pinfunction "2_K") (pintype "passive"))
      (node (ref "ACS1") (pin "5") (pinfunction "GND_5") (pintype "passive"))
      (node (ref "AO1") (pin "4") (pinfunction "S1_4") (pintype "passive"))
      (node (ref "AO2") (pin "4") (pinfunction "S1_4") (pintype "passive"))
      (node (ref "C11") (pin "2") (pinfunction "2_2") (pintype "passive"))
      (node (ref "C12") (pin "1") (pinfunction "1_1") (pintype "passive"))
      (node (ref "C13") (pin "1") (pinfunction "1_1") (pintype "passive"))
      (node (ref "C21") (pin "2") (pinfunction "2_2") (pintype "passive"))
      (node (ref "C22") (pin "2") (pinfunction "2_2") (pintype "passive"))
      (node (ref "C23") (pin "2") (pinfunction "2_2") (pintype "passive"))
      (node (ref "C24") (pin "2") (pinfunction "2_2") (pintype "passive"))
      (node (ref "C6") (pin "1") (pinfunction "1_1") (pintype "passive"))
      (node (ref "CV1") (pin "2") (pinfunction "2_2") (pintype "passive"))
      (node (ref "D6") (pin "1") (pinfunction "A_1") (pintype "passive"))
      (node (ref "IR1") (pin "4") (pinfunction "COM_4") (pintype "passive"))
      (node (ref "IR2") (pin "4") (pinfunction "COM_4") (pintype "passive"))
      (node (ref "LM1") (pin "2") (pinfunction "GND_2") (pintype "passive"))
      (node (ref "MP1") (pin "2") (pinfunction "GND_2") (pintype "passive"))
      (node (ref "P4") (pin "5") (pinfunction "5_5") (pintype "passive"))
      (node (ref "P7") (pin "2") (pinfunction "2_2") (pintype "passive"))
      (node (ref "P8") (pin "6") (pinfunction "6_6") (pintype "passive"))
      (node (ref "R10") (pin "2") (pinfunction "2_2") (pintype "passive"))
      (node (ref "R12") (pin "2") (pinfunction "2_2") (pintype "passive"))
      (node (ref "R13") (pin "2") (pinfunction "2_2") (pintype "passive"))
      (node (ref "R16") (pin "2") (pinfunction "2_2") (pintype "passive"))
      (node (ref "R19") (pin "2") (pinfunction "2_2") (pintype "passive"))
      (node (ref "R26") (pin "1") (pinfunction "1_1") (pintype "passive"))
      (node (ref "R27") (pin "1") (pinfunction "1_1") (pintype "passive"))
      (node (ref "TJA1") (pin "2") (pinfunction "GND_2") (pintype "passive"))
      (node (ref "TJA1") (pin "8") (pinfunction "S_8") (pintype "passive"))
    )
    (net (code "67") (name "VIN") (class "Default")
      (node (ref "24V") (pin "A") (pinfunction "1_A") (pintype "passive"))
      (node (ref "AO1") (pin "1") (pinfunction "D2_1") (pintype "passive"))
      (node (ref "AO1") (pin "2") (pinfunction "D2_2") (pintype "passive"))
      (node (ref "AO2") (pin "1") (pinfunction "D2_1") (pintype "passive"))
      (node (ref "AO2") (pin "2") (pinfunction "D2_2") (pintype "passive"))
      (node (ref "C13") (pin "2") (pinfunction "2_2") (pintype "passive"))
      (node (ref "CV1") (pin "1") (pinfunction "1_1") (pintype "passive"))
      (node (ref "MP1") (pin "5") (pinfunction "VIN_5") (pintype "passive"))
      (node (ref "P7") (pin "1") (pinfunction "1_1") (pintype "passive"))
      (node (ref "R11") (pin "1") (pinfunction "1_1") (pintype "passive"))
    )
    (net (code "68") (name "unconnected-(TJA1-Vref-Pad5)") (class "Default")
      (node (ref "TJA1") (pin "5") (pinfunction "Vref_5") (pintype "passive"))
    )
    (net (code "69") (name "unconnected-(U1-PA2{slash}USART2_TX{slash}ADC2-Pad16)") (class "Default")
      (node (ref "U1") (pin "16") (pinfunction "PA2/USART2_TX/ADC2_16") (pintype "passive"))
    )
    (net (code "70") (name "unconnected-(U1-PA3{slash}USART2_RX{slash}ADC3-Pad17)") (class "Default")
      (node (ref "U1") (pin "17") (pinfunction "PA3/USART2_RX/ADC3_17") (pintype "passive"))
    )
    (net (code "71") (name "unconnected-(U1-PA5{slash}SPI1_SCK-Pad21)") (class "Default")
      (node (ref "U1") (pin "21") (pinfunction "PA5/SPI1_SCK_21") (pintype "passive"))
    )
    (net (code "72") (name "unconnected-(U1-PA6{slash}SPI1_MISO-Pad22)") (class "Default")
      (node (ref "U1") (pin "22") (pinfunction "PA6/SPI1_MISO_22") (pintype "passive"))
    )
    (net (code "73") (name "unconnected-(U1-PA7{slash}SPI1_MOSI-Pad23)") (class "Default")
      (node (ref "U1") (pin "23") (pinfunction "PA7/SPI1_MOSI_23") (pintype "passive"))
    )
    (net (code "74") (name "unconnected-(U1-PA8{slash}USART1_CK-Pad41)") (class "Default")
      (node (ref "U1") (pin "41") (pinfunction "PA8/USART1_CK_41") (pintype "passive"))
    )
    (net (code "75") (name "unconnected-(U1-PA15{slash}JTDI-Pad50)") (class "Default")
      (node (ref "U1") (pin "50") (pinfunction "PA15/JTDI_50") (pintype "passive"))
    )
    (net (code "76") (name "unconnected-(U1-PB1{slash}ADC9-Pad27)") (class "Default")
      (node (ref "U1") (pin "27") (pinfunction "PB1/ADC9_27") (pintype "passive"))
    )
    (net (code "77") (name "unconnected-(U1-PB3{slash}JTDO-Pad55)") (class "Default")
      (node (ref "U1") (pin "55") (pinfunction "PB3/JTDO_55") (pintype "passive"))
    )
    (net (code "78") (name "unconnected-(U1-PB4{slash}JNTRST-Pad56)") (class "Default")
      (node (ref "U1") (pin "56") (pinfunction "PB4/JNTRST_56") (pintype "passive"))
    )
    (net (code "79") (name "unconnected-(U1-PB5-Pad57)") (class "Default")
      (node (ref "U1") (pin "57") (pinfunction "PB5_57") (pintype "passive"))
    )
    (net (code "80") (name "unconnected-(U1-PC0{slash}ADC10-Pad8)") (class "Default")
      (node (ref "U1") (pin "8") (pinfunction "PC0/ADC10_8") (pintype "passive"))
    )
    (net (code "81") (name "unconnected-(U1-PC1{slash}ADC11-Pad9)") (class "Default")
      (node (ref "U1") (pin "9") (pinfunction "PC1/ADC11_9") (pintype "passive"))
    )
    (net (code "82") (name "unconnected-(U1-PC2{slash}ADC12-Pad10)") (class "Default")
      (node (ref "U1") (pin "10") (pinfunction "PC2/ADC12_10") (pintype "passive"))
    )
    (net (code "83") (name "unconnected-(U1-PC3{slash}ADC13-Pad11)") (class "Default")
      (node (ref "U1") (pin "11") (pinfunction "PC3/ADC13_11") (pintype "passive"))
    )
    (net (code "84") (name "unconnected-(U1-PC4{slash}ADC14-Pad24)") (class "Default")
      (node (ref "U1") (pin "24") (pinfunction "PC4/ADC14_24") (pintype "passive"))
    )
    (net (code "85") (name "unconnected-(U1-PC6-Pad37)") (class "Default")
      (node (ref "U1") (pin "37") (pinfunction "PC6_37") (pintype "passive"))
    )
    (net (code "86") (name "unconnected-(U1-PC9-Pad40)") (class "Default")
      (node (ref "U1") (pin "40") (pinfunction "PC9_40") (pintype "passive"))
    )
    (net (code "87") (name "unconnected-(U1-PC10-Pad51)") (class "Default")
      (node (ref "U1") (pin "51") (pinfunction "PC10_51") (pintype "passive"))
    )
    (net (code "88") (name "unconnected-(U1-PC11-Pad52)") (class "Default")
      (node (ref "U1") (pin "52") (pinfunction "PC11_52") (pintype "passive"))
    )
    (net (code "89") (name "unconnected-(U1-PC12-Pad53)") (class "Default")
      (node (ref "U1") (pin "53") (pinfunction "PC12_53") (pintype "passive"))
    )
    (net (code "90") (name "unconnected-(U1-PC13-TAMPER-RTC-Pad2)") (class "Default")
      (node (ref "U1") (pin "2") (pinfunction "PC13-TAMPER-RTC_2") (pintype "passive"))
    )
    (net (code "91") (name "unconnected-(U1-PC14{slash}OSC32-Pad3)") (class "Default")
      (node (ref "U1") (pin "3") (pinfunction "PC14/OSC32_3") (pintype "passive"))
    )
    (net (code "92") (name "unconnected-(U1-PC15{slash}OSC32-Pad4)") (class "Default")
      (node (ref "U1") (pin "4") (pinfunction "PC15/OSC32_4") (pintype "passive"))
    )
    (net (code "93") (name "unconnected-(U1-PD2-Pad54)") (class "Default")
      (node (ref "U1") (pin "54") (pinfunction "PD2_54") (pintype "passive"))
    )
  )
)
